# Sheet1.net
KiCad netlist of a schematic drawn in Altium Designer
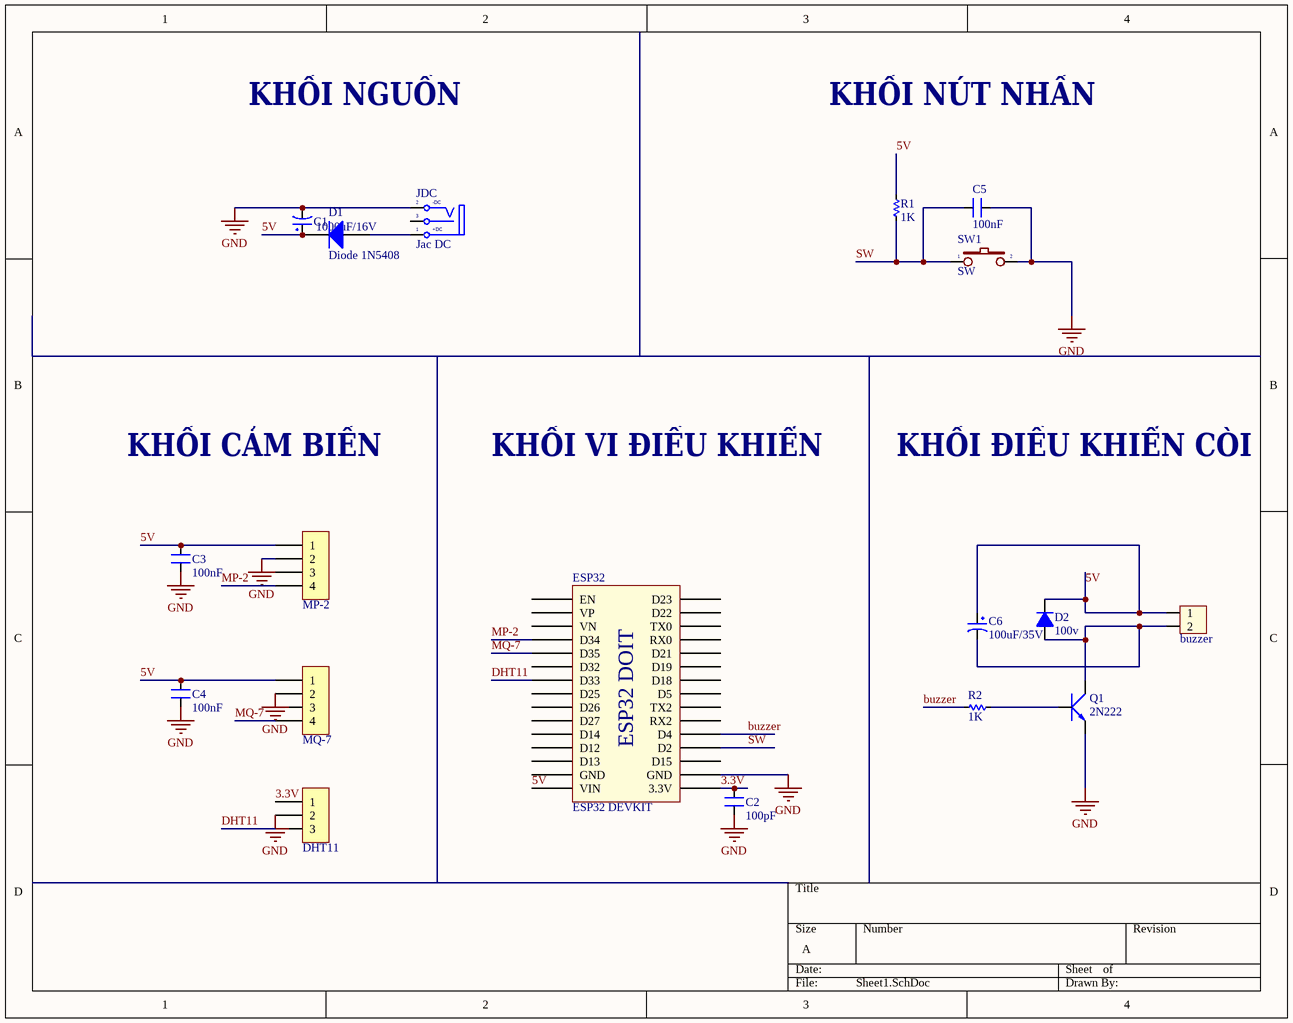
[diagram p0: Sheet1.SchDoc]

(export (version "E")
  (design (tool "Eeschema 10.0.6"))
  (components
    (comp (ref "buzzer")
      (value "buzzer")
      (footprint "XH2.54M-2")
      (description "Cắm")
      (libsource (lib "Header") (part "Header 2P 2.54 Duc Thang"))
    )
    (comp (ref "C1")
      (value "1000uF/16V")
      (footprint "CP1.5/3.4")
      (description "Cap 1000uF/16V - 220uF/50V")
      (libsource (lib "syhaunguyen") (part "CP4"))
    )
    (comp (ref "C2")
      (value "100pF")
      (footprint "CN1")
      (description "Cap np  1pF - 472pF")
      (libsource (lib "syhaunguyen") (part "CN1"))
    )
    (comp (ref "C3")
      (value "100nF")
      (footprint "CN1")
      (description "Cap np  1pF - 472pF")
      (libsource (lib "syhaunguyen") (part "CN1"))
    )
    (comp (ref "C4")
      (value "100nF")
      (footprint "CN1")
      (description "Cap np  1pF - 472pF")
      (libsource (lib "syhaunguyen") (part "CN1"))
    )
    (comp (ref "C5")
      (value "100nF")
      (footprint "CN1")
      (description "Cap np  1pF - 472pF")
      (libsource (lib "syhaunguyen") (part "CN1"))
    )
    (comp (ref "C6")
      (value "100uF/35V")
      (footprint "CP1.5/3.4")
      (description "Cap 100uF/35V - 470uF/16V")
      (libsource (lib "syhaunguyen") (part "CP3"))
    )
    (comp (ref "D1")
      (value "Diode 1N5408")
      (footprint "DO-201AD")
      (description "3 Amp Medium Power Silicon Rectifier Diode")
      (fields (field (name "PUBLISHER") "Altium Limited"))
      (libsource (lib "Miscellaneous Devices") (part "Diode 1N5408"))
    )
    (comp (ref "D2")
      (value "100v")
      (footprint "DIODE 0.5A")
      (description "Cắm")
      (libsource (lib "Diode") (part "Diode 1N4148"))
    )
    (comp (ref "DHT11")
      (value "DHT11")
      (footprint "XH2.54M-3")
      (description "Cắm")
      (libsource (lib "Header") (part "Header 3P 2.54 Duc Thang"))
    )
    (comp (ref "ESP32")
      (value "ESP32 DEVKIT")
      (footprint "ESP32 WROOM 32 KIT")
      (libsource (lib "Module") (part "ESP32 WROOM 32 KIT"))
    )
    (comp (ref "JDC")
      (value "Jac DC")
      (footprint "DC-IN")
      (description "Jac DC input")
      (libsource (lib "syhaunguyen") (part "DCIN"))
    )
    (comp (ref "MP-2")
      (value "MP-2")
      (footprint "XH2.54M-4")
      (description "Cắm")
      (libsource (lib "Header") (part "Header 4P 2.54 Duc Thang"))
    )
    (comp (ref "MQ-7")
      (value "MQ-7")
      (footprint "XH2.54M-4")
      (description "Cắm")
      (libsource (lib "Header") (part "Header 4P 2.54 Duc Thang"))
    )
    (comp (ref "Q1")
      (value "2N222")
      (footprint "TO92-123")
      (description "NPN 600mW, ECB")
      (libsource (lib "Altium Library") (part "2N222"))
    )
    (comp (ref "R1")
      (value "1K")
      (footprint "RES-1/2W")
      (description "Res")
      (fields
        (field (name "MANUFACTURER") "Generic Components")
        (field (name "PUBLISHER") "Altium Hobart Technology Centre")
      )
      (libsource (lib "Altium Library") (part "Res"))
    )
    (comp (ref "R2")
      (value "1K")
      (footprint "RES-1/2W")
      (description "Res")
      (fields
        (field (name "MANUFACTURER") "Generic Components")
        (field (name "PUBLISHER") "Altium Hobart Technology Centre")
      )
      (libsource (lib "Altium Library") (part "Res"))
    )
    (comp (ref "SW1")
      (value "SW")
      (footprint "SW2")
      (description "Switch button 2 pin")
      (libsource (lib "syhaunguyen") (part "SW2"))
    )
  )
  (nets
    (net (code "1") (name "/3.3V") (class "Default")
      (node (ref "C2") (pin "2") (pinfunction "2_2") (pintype "passive"))
      (node (ref "DHT11") (pin "1") (pinfunction "1_1") (pintype "passive"))
      (node (ref "ESP32") (pin "16") (pinfunction "3.3V_16") (pintype "passive"))
    )
    (net (code "2") (name "/5V") (class "Default")
      (node (ref "C1") (pin "1") (pinfunction "1_1") (pintype "passive"))
      (node (ref "C3") (pin "2") (pinfunction "2_2") (pintype "passive"))
      (node (ref "C4") (pin "1") (pinfunction "1_1") (pintype "passive"))
      (node (ref "C6") (pin "1") (pinfunction "1_1") (pintype "passive"))
      (node (ref "D1") (pin "2") (pinfunction "K_2") (pintype "passive"))
      (node (ref "D2") (pin "2") (pinfunction "K_2") (pintype "passive"))
      (node (ref "ESP32") (pin "15") (pinfunction "VIN_15") (pintype "passive"))
      (node (ref "MP-2") (pin "1") (pinfunction "1_1") (pintype "passive"))
      (node (ref "MQ-7") (pin "1") (pinfunction "1_1") (pintype "passive"))
      (node (ref "R1") (pin "1") (pinfunction "1_1") (pintype "passive"))
      (node (ref "buzzer") (pin "1") (pinfunction "1_1") (pintype "passive"))
    )
    (net (code "3") (name "/DHT11") (class "Default")
      (node (ref "DHT11") (pin "3") (pinfunction "3_3") (pintype "passive"))
      (node (ref "ESP32") (pin "7") (pinfunction "D33_7") (pintype "passive"))
    )
    (net (code "4") (name "/MP-2") (class "Default")
      (node (ref "ESP32") (pin "4") (pinfunction "D34_4") (pintype "passive"))
      (node (ref "MP-2") (pin "4") (pinfunction "4_4") (pintype "passive"))
    )
    (net (code "5") (name "/MQ-7") (class "Default")
      (node (ref "ESP32") (pin "5") (pinfunction "D35_5") (pintype "passive"))
      (node (ref "MQ-7") (pin "4") (pinfunction "4_4") (pintype "passive"))
    )
    (net (code "6") (name "/SW") (class "Default")
      (node (ref "C5") (pin "2") (pinfunction "2_2") (pintype "passive"))
      (node (ref "ESP32") (pin "19") (pinfunction "D2_19") (pintype "passive"))
      (node (ref "R1") (pin "2") (pinfunction "2_2") (pintype "passive"))
      (node (ref "SW1") (pin "1") (pinfunction "1_1") (pintype "passive"))
    )
    (net (code "7") (name "/buzzer") (class "Default")
      (node (ref "ESP32") (pin "20") (pinfunction "D4_20") (pintype "passive"))
      (node (ref "R2") (pin "1") (pinfunction "1_1") (pintype "passive"))
    )
    (net (code "8") (name "GND") (class "Default")
      (node (ref "C1") (pin "2") (pinfunction "2_2") (pintype "passive"))
      (node (ref "C2") (pin "1") (pinfunction "1_1") (pintype "passive"))
      (node (ref "C3") (pin "1") (pinfunction "1_1") (pintype "passive"))
      (node (ref "C4") (pin "2") (pinfunction "2_2") (pintype "passive"))
      (node (ref "C5") (pin "1") (pinfunction "1_1") (pintype "passive"))
      (node (ref "DHT11") (pin "2") (pinfunction "2_2") (pintype "passive"))
      (node (ref "ESP32") (pin "17") (pinfunction "GND_17") (pintype "passive"))
      (node (ref "JDC") (pin "2") (pinfunction "TN_2") (pintype "passive"))
      (node (ref "MP-2") (pin "2") (pinfunction "2_2") (pintype "passive"))
      (node (ref "MQ-7") (pin "2") (pinfunction "2_2") (pintype "passive"))
      (node (ref "Q1") (pin "1") (pinfunction "E_1") (pintype "passive"))
      (node (ref "SW1") (pin "2") (pinfunction "2_2") (pintype "passive"))
    )
    (net (code "9") (name "Net-(D1-A)") (class "Default")
      (node (ref "D1") (pin "1") (pinfunction "A_1") (pintype "passive"))
      (node (ref "JDC") (pin "1") (pinfunction "T_1") (pintype "passive"))
    )
    (net (code "10") (name "Net-(D2-A)") (class "Default")
      (node (ref "C6") (pin "2") (pinfunction "2_2") (pintype "passive"))
      (node (ref "D2") (pin "1") (pinfunction "A_1") (pintype "passive"))
      (node (ref "Q1") (pin "3") (pinfunction "C_3") (pintype "passive"))
      (node (ref "buzzer") (pin "2") (pinfunction "2_2") (pintype "passive"))
    )
    (net (code "11") (name "Net-(Q1-B)") (class "Default")
      (node (ref "Q1") (pin "2") (pinfunction "B_2") (pintype "passive"))
      (node (ref "R2") (pin "2") (pinfunction "2_2") (pintype "passive"))
    )
    (net (code "12") (name "unconnected-(ESP32-D5-Pad23)") (class "Default")
      (node (ref "ESP32") (pin "23") (pinfunction "D5_23") (pintype "passive"))
    )
    (net (code "13") (name "unconnected-(ESP32-D12-Pad12)") (class "Default")
      (node (ref "ESP32") (pin "12") (pinfunction "D12_12") (pintype "passive"))
    )
    (net (code "14") (name "unconnected-(ESP32-D13-Pad13)") (class "Default")
      (node (ref "ESP32") (pin "13") (pinfunction "D13_13") (pintype "passive"))
    )
    (net (code "15") (name "unconnected-(ESP32-D14-Pad11)") (class "Default")
      (node (ref "ESP32") (pin "11") (pinfunction "D14_11") (pintype "passive"))
    )
    (net (code "16") (name "unconnected-(ESP32-D15-Pad18)") (class "Default")
      (node (ref "ESP32") (pin "18") (pinfunction "D15_18") (pintype "passive"))
    )
    (net (code "17") (name "unconnected-(ESP32-D18-Pad24)") (class "Default")
      (node (ref "ESP32") (pin "24") (pinfunction "D18_24") (pintype "passive"))
    )
    (net (code "18") (name "unconnected-(ESP32-D19-Pad25)") (class "Default")
      (node (ref "ESP32") (pin "25") (pinfunction "D19_25") (pintype "passive"))
    )
    (net (code "19") (name "unconnected-(ESP32-D21-Pad26)") (class "Default")
      (node (ref "ESP32") (pin "26") (pinfunction "D21_26") (pintype "passive"))
    )
    (net (code "20") (name "unconnected-(ESP32-D22-Pad29)") (class "Default")
      (node (ref "ESP32") (pin "29") (pinfunction "D22_29") (pintype "passive"))
    )
    (net (code "21") (name "unconnected-(ESP32-D23-Pad30)") (class "Default")
      (node (ref "ESP32") (pin "30") (pinfunction "D23_30") (pintype "passive"))
    )
    (net (code "22") (name "unconnected-(ESP32-D25-Pad8)") (class "Default")
      (node (ref "ESP32") (pin "8") (pinfunction "D25_8") (pintype "passive"))
    )
    (net (code "23") (name "unconnected-(ESP32-D26-Pad9)") (class "Default")
      (node (ref "ESP32") (pin "9") (pinfunction "D26_9") (pintype "passive"))
    )
    (net (code "24") (name "unconnected-(ESP32-D27-Pad10)") (class "Default")
      (node (ref "ESP32") (pin "10") (pinfunction "D27_10") (pintype "passive"))
    )
    (net (code "25") (name "unconnected-(ESP32-D32-Pad6)") (class "Default")
      (node (ref "ESP32") (pin "6") (pinfunction "D32_6") (pintype "passive"))
    )
    (net (code "26") (name "unconnected-(ESP32-EN-Pad1)") (class "Default")
      (node (ref "ESP32") (pin "1") (pinfunction "EN_1") (pintype "passive"))
    )
    (net (code "27") (name "unconnected-(ESP32-GND-Pad14)") (class "Default")
      (node (ref "ESP32") (pin "14") (pinfunction "GND_14") (pintype "passive"))
    )
    (net (code "28") (name "unconnected-(ESP32-RX0-Pad27)") (class "Default")
      (node (ref "ESP32") (pin "27") (pinfunction "RX0_27") (pintype "passive"))
    )
    (net (code "29") (name "unconnected-(ESP32-RX2-Pad21)") (class "Default")
      (node (ref "ESP32") (pin "21") (pinfunction "RX2_21") (pintype "passive"))
    )
    (net (code "30") (name "unconnected-(ESP32-TX0-Pad28)") (class "Default")
      (node (ref "ESP32") (pin "28") (pinfunction "TX0_28") (pintype "passive"))
    )
    (net (code "31") (name "unconnected-(ESP32-TX2-Pad22)") (class "Default")
      (node (ref "ESP32") (pin "22") (pinfunction "TX2_22") (pintype "passive"))
    )
    (net (code "32") (name "unconnected-(ESP32-VN-Pad3)") (class "Default")
      (node (ref "ESP32") (pin "3") (pinfunction "VN_3") (pintype "passive"))
    )
    (net (code "33") (name "unconnected-(ESP32-VP-Pad2)") (class "Default")
      (node (ref "ESP32") (pin "2") (pinfunction "VP_2") (pintype "passive"))
    )
    (net (code "34") (name "unconnected-(JDC-S-Pad3)") (class "Default")
      (node (ref "JDC") (pin "3") (pinfunction "S_3") (pintype "power_in"))
    )
    (net (code "35") (name "unconnected-(MP-2-Pad3)") (class "Default")
      (node (ref "MP-2") (pin "3") (pinfunction "3_3") (pintype "passive"))
    )
    (net (code "36") (name "unconnected-(MQ-7-Pad3)") (class "Default")
      (node (ref "MQ-7") (pin "3") (pinfunction "3_3") (pintype "passive"))
    )
  )
)
